# ETRX_RECU.net
KiCad netlist of a schematic drawn in Altium Designer
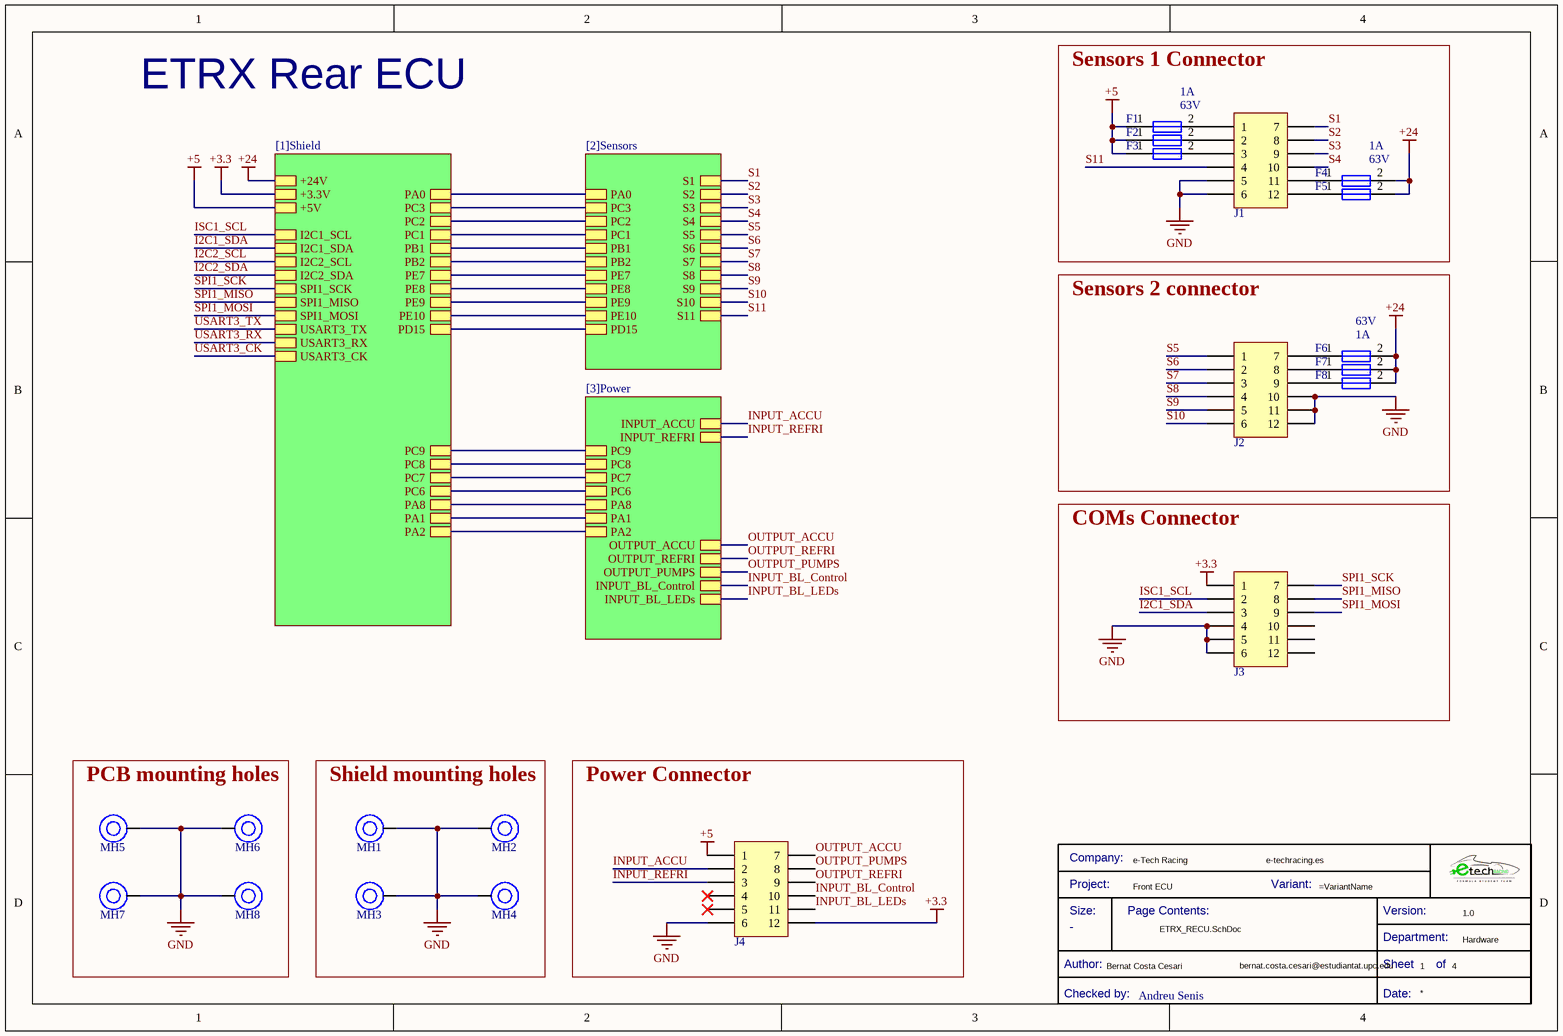
[diagram p0: ETRX_RECU.SchDoc]

(export (version "E")
  (design (tool "Eeschema 10.0.6"))
  (components
    (comp (ref "F1")
      (value "0437001.WRA")
      (footprint "Fuse_1206")
      (description "Fuse Chip Fast Acting 1A 63V SMD Solder Pad 1206 Ceramic T/R Automotive")
      (fields
        (field (name "MANUFACTURER") "Littelfuse")
        (field (name "CURRENT RATING") "1A")
        (field (name "VOLTAGE RATING (DC)") "63V")
        (field (name ".CREATOR") "DO")
      )
      (libsource (lib "Filter components") (part "Fuse_1A_63V_1206"))
    )
    (comp (ref "F2")
      (value "0437001.WRA")
      (footprint "Fuse_1206")
      (description "Fuse Chip Fast Acting 1A 63V SMD Solder Pad 1206 Ceramic T/R Automotive")
      (fields (field (name "MANUFACTURER") "Littelfuse") (field (name ".CREATOR") "DO"))
      (libsource (lib "Filter components") (part "Fuse_1A_63V_1206"))
    )
    (comp (ref "F3")
      (value "0437001.WRA")
      (footprint "Fuse_1206")
      (description "Fuse Chip Fast Acting 1A 63V SMD Solder Pad 1206 Ceramic T/R Automotive")
      (fields (field (name "MANUFACTURER") "Littelfuse") (field (name ".CREATOR") "DO"))
      (libsource (lib "Filter components") (part "Fuse_1A_63V_1206"))
    )
    (comp (ref "F4")
      (value "0437001.WRA")
      (footprint "Fuse_1206")
      (description "Fuse Chip Fast Acting 1A 63V SMD Solder Pad 1206 Ceramic T/R Automotive")
      (fields
        (field (name "MANUFACTURER") "Littelfuse")
        (field (name "CURRENT RATING") "1A")
        (field (name "VOLTAGE RATING (DC)") "63V")
        (field (name ".CREATOR") "DO")
      )
      (libsource (lib "Filter components") (part "Fuse_1A_63V_1206"))
    )
    (comp (ref "F5")
      (value "0437001.WRA")
      (footprint "Fuse_1206")
      (description "Fuse Chip Fast Acting 1A 63V SMD Solder Pad 1206 Ceramic T/R Automotive")
      (fields (field (name "MANUFACTURER") "Littelfuse") (field (name ".CREATOR") "DO"))
      (libsource (lib "Filter components") (part "Fuse_1A_63V_1206"))
    )
    (comp (ref "F6")
      (value "0437001.WRA")
      (footprint "Fuse_1206")
      (description "Fuse Chip Fast Acting 1A 63V SMD Solder Pad 1206 Ceramic T/R Automotive")
      (fields
        (field (name "MANUFACTURER") "Littelfuse")
        (field (name "CURRENT RATING") "1A")
        (field (name "VOLTAGE RATING (DC)") "63V")
        (field (name ".CREATOR") "DO")
      )
      (libsource (lib "Filter components") (part "Fuse_1A_63V_1206"))
    )
    (comp (ref "F7")
      (value "0437001.WRA")
      (footprint "Fuse_1206")
      (description "Fuse Chip Fast Acting 1A 63V SMD Solder Pad 1206 Ceramic T/R Automotive")
      (fields (field (name "MANUFACTURER") "Littelfuse") (field (name ".CREATOR") "DO"))
      (libsource (lib "Filter components") (part "Fuse_1A_63V_1206"))
    )
    (comp (ref "F8")
      (value "0437001.WRA")
      (footprint "Fuse_1206")
      (description "Fuse Chip Fast Acting 1A 63V SMD Solder Pad 1206 Ceramic T/R Automotive")
      (fields (field (name "MANUFACTURER") "Littelfuse") (field (name ".CREATOR") "DO"))
      (libsource (lib "Filter components") (part "Fuse_1A_63V_1206"))
    )
    (comp (ref "J1")
      (value "1053101112")
      (footprint "J_NanoFit_2x6_V")
      (libsource (lib "Electromechanical") (part "J_NanoFit_2x6_V"))
    )
    (comp (ref "J2")
      (value "1053101112")
      (footprint "J_NanoFit_2x6_V")
      (libsource (lib "Electromechanical") (part "J_NanoFit_2x6_V"))
    )
    (comp (ref "J3")
      (value "1053101112")
      (footprint "J_NanoFit_2x6_V")
      (libsource (lib "Electromechanical") (part "J_NanoFit_2x6_V"))
    )
    (comp (ref "J4")
      (value "1053101112")
      (footprint "J_NanoFit_2x6_V")
      (libsource (lib "Electromechanical") (part "J_NanoFit_2x6_V"))
    )
    (comp (ref "MH1")
      (value "Mounting_Hole_M3")
      (footprint "Mounting_Hole_M3")
      (libsource (lib "Electromechanical") (part "Mounting_Hole_M3"))
    )
    (comp (ref "MH2")
      (value "Mounting_Hole_M3")
      (footprint "Mounting_Hole_M3")
      (libsource (lib "Electromechanical") (part "Mounting_Hole_M3"))
    )
    (comp (ref "MH3")
      (value "Mounting_Hole_M3")
      (footprint "Mounting_Hole_M3")
      (libsource (lib "Electromechanical") (part "Mounting_Hole_M3"))
    )
    (comp (ref "MH4")
      (value "Mounting_Hole_M3")
      (footprint "Mounting_Hole_M3")
      (libsource (lib "Electromechanical") (part "Mounting_Hole_M3"))
    )
    (comp (ref "MH5")
      (value "Mounting_Hole_M4")
      (footprint "Mounting_Hole_M4")
      (libsource (lib "Electromechanical") (part "Mounting_Hole_M4"))
    )
    (comp (ref "MH6")
      (value "Mounting_Hole_M4")
      (footprint "Mounting_Hole_M4")
      (libsource (lib "Electromechanical") (part "Mounting_Hole_M4"))
    )
    (comp (ref "MH7")
      (value "Mounting_Hole_M4")
      (footprint "Mounting_Hole_M4")
      (libsource (lib "Electromechanical") (part "Mounting_Hole_M4"))
    )
    (comp (ref "MH8")
      (value "Mounting_Hole_M4")
      (footprint "Mounting_Hole_M4")
      (libsource (lib "Electromechanical") (part "Mounting_Hole_M4"))
    )
  )
  (nets
    (net (code "1") (name "+3.3") (class "Default")
      (node (ref "J3") (pin "1") (pinfunction "1_1") (pintype "passive"))
      (node (ref "J4") (pin "12") (pinfunction "12_12") (pintype "passive"))
    )
    (net (code "2") (name "+5") (class "Default")
      (node (ref "F1") (pin "1") (pinfunction "1_1") (pintype "passive"))
      (node (ref "F2") (pin "1") (pinfunction "1_1") (pintype "passive"))
      (node (ref "F3") (pin "1") (pinfunction "1_1") (pintype "passive"))
      (node (ref "J4") (pin "1") (pinfunction "1_1") (pintype "passive"))
    )
    (net (code "3") (name "+24") (class "Default")
      (node (ref "F4") (pin "2") (pinfunction "2_2") (pintype "passive"))
      (node (ref "F5") (pin "2") (pinfunction "2_2") (pintype "passive"))
      (node (ref "F6") (pin "2") (pinfunction "2_2") (pintype "passive"))
      (node (ref "F7") (pin "2") (pinfunction "2_2") (pintype "passive"))
      (node (ref "F8") (pin "2") (pinfunction "2_2") (pintype "passive"))
    )
    (net (code "4") (name "/I2C1_SDA") (class "Default")
      (node (ref "J3") (pin "3") (pinfunction "3_3") (pintype "passive"))
    )
    (net (code "7") (name "/INPUT_ACCU") (class "Default")
      (node (ref "J4") (pin "2") (pinfunction "2_2") (pintype "passive"))
    )
    (net (code "8") (name "/INPUT_BL_Control") (class "Default")
      (node (ref "J4") (pin "10") (pinfunction "10_10") (pintype "passive"))
    )
    (net (code "9") (name "/INPUT_BL_LEDs") (class "Default")
      (node (ref "J4") (pin "11") (pinfunction "11_11") (pintype "passive"))
    )
    (net (code "10") (name "/INPUT_REFRI") (class "Default")
      (node (ref "J4") (pin "3") (pinfunction "3_3") (pintype "passive"))
    )
    (net (code "11") (name "/ISC1_SCL") (class "Default")
      (node (ref "J3") (pin "2") (pinfunction "2_2") (pintype "passive"))
    )
    (net (code "12") (name "/OUTPUT_ACCU") (class "Default")
      (node (ref "J4") (pin "7") (pinfunction "7_7") (pintype "passive"))
    )
    (net (code "13") (name "/OUTPUT_PUMPS") (class "Default")
      (node (ref "J4") (pin "8") (pinfunction "8_8") (pintype "passive"))
    )
    (net (code "14") (name "/OUTPUT_REFRI") (class "Default")
      (node (ref "J4") (pin "9") (pinfunction "9_9") (pintype "passive"))
    )
    (net (code "33") (name "/S1") (class "Default")
      (node (ref "J1") (pin "7") (pinfunction "7_7") (pintype "passive"))
    )
    (net (code "34") (name "/S2") (class "Default")
      (node (ref "J1") (pin "8") (pinfunction "8_8") (pintype "passive"))
    )
    (net (code "35") (name "/S3") (class "Default")
      (node (ref "J1") (pin "9") (pinfunction "9_9") (pintype "passive"))
    )
    (net (code "36") (name "/S4") (class "Default")
      (node (ref "J1") (pin "10") (pinfunction "10_10") (pintype "passive"))
    )
    (net (code "37") (name "/S5") (class "Default")
      (node (ref "J2") (pin "1") (pinfunction "1_1") (pintype "passive"))
    )
    (net (code "38") (name "/S6") (class "Default")
      (node (ref "J2") (pin "2") (pinfunction "2_2") (pintype "passive"))
    )
    (net (code "39") (name "/S7") (class "Default")
      (node (ref "J2") (pin "3") (pinfunction "3_3") (pintype "passive"))
    )
    (net (code "40") (name "/S8") (class "Default")
      (node (ref "J2") (pin "4") (pinfunction "4_4") (pintype "passive"))
    )
    (net (code "41") (name "/S9") (class "Default")
      (node (ref "J2") (pin "5") (pinfunction "5_5") (pintype "passive"))
    )
    (net (code "42") (name "/S10") (class "Default")
      (node (ref "J2") (pin "6") (pinfunction "6_6") (pintype "passive"))
    )
    (net (code "43") (name "/S11") (class "Default")
      (node (ref "J1") (pin "4") (pinfunction "4_4") (pintype "passive"))
    )
    (net (code "44") (name "/SPI1_MISO") (class "Default")
      (node (ref "J3") (pin "8") (pinfunction "8_8") (pintype "passive"))
    )
    (net (code "45") (name "/SPI1_MOSI") (class "Default")
      (node (ref "J3") (pin "9") (pinfunction "9_9") (pintype "passive"))
    )
    (net (code "46") (name "/SPI1_SCK") (class "Default")
      (node (ref "J3") (pin "7") (pinfunction "7_7") (pintype "passive"))
    )
    (net (code "50") (name "GND") (class "Default")
      (node (ref "J1") (pin "5") (pinfunction "5_5") (pintype "passive"))
      (node (ref "J1") (pin "6") (pinfunction "6_6") (pintype "passive"))
      (node (ref "J2") (pin "10") (pinfunction "10_10") (pintype "passive"))
      (node (ref "J2") (pin "11") (pinfunction "11_11") (pintype "passive"))
      (node (ref "J2") (pin "12") (pinfunction "12_12") (pintype "passive"))
      (node (ref "J3") (pin "4") (pinfunction "4_4") (pintype "passive"))
      (node (ref "J3") (pin "5") (pinfunction "5_5") (pintype "passive"))
      (node (ref "J3") (pin "6") (pinfunction "6_6") (pintype "passive"))
      (node (ref "J4") (pin "6") (pinfunction "6_6") (pintype "passive"))
      (node (ref "MH1") (pin "1") (pinfunction "1_1") (pintype "passive"))
      (node (ref "MH2") (pin "1") (pinfunction "1_1") (pintype "passive"))
      (node (ref "MH3") (pin "1") (pinfunction "1_1") (pintype "passive"))
      (node (ref "MH4") (pin "1") (pinfunction "1_1") (pintype "passive"))
      (node (ref "MH5") (pin "1") (pinfunction "1_1") (pintype "passive"))
      (node (ref "MH6") (pin "1") (pinfunction "1_1") (pintype "passive"))
      (node (ref "MH7") (pin "1") (pinfunction "1_1") (pintype "passive"))
      (node (ref "MH8") (pin "1") (pinfunction "1_1") (pintype "passive"))
    )
    (net (code "51") (name "Net-(F1-Pad2)") (class "Default")
      (node (ref "F1") (pin "2") (pinfunction "2_2") (pintype "passive"))
      (node (ref "J1") (pin "1") (pinfunction "1_1") (pintype "passive"))
    )
    (net (code "52") (name "Net-(F2-Pad2)") (class "Default")
      (node (ref "F2") (pin "2") (pinfunction "2_2") (pintype "passive"))
      (node (ref "J1") (pin "2") (pinfunction "2_2") (pintype "passive"))
    )
    (net (code "53") (name "Net-(F3-Pad2)") (class "Default")
      (node (ref "F3") (pin "2") (pinfunction "2_2") (pintype "passive"))
      (node (ref "J1") (pin "3") (pinfunction "3_3") (pintype "passive"))
    )
    (net (code "54") (name "Net-(F4-Pad1)") (class "Default")
      (node (ref "F4") (pin "1") (pinfunction "1_1") (pintype "passive"))
      (node (ref "J1") (pin "11") (pinfunction "11_11") (pintype "passive"))
    )
    (net (code "55") (name "Net-(F5-Pad1)") (class "Default")
      (node (ref "F5") (pin "1") (pinfunction "1_1") (pintype "passive"))
      (node (ref "J1") (pin "12") (pinfunction "12_12") (pintype "passive"))
    )
    (net (code "56") (name "Net-(F6-Pad1)") (class "Default")
      (node (ref "F6") (pin "1") (pinfunction "1_1") (pintype "passive"))
      (node (ref "J2") (pin "7") (pinfunction "7_7") (pintype "passive"))
    )
    (net (code "57") (name "Net-(F7-Pad1)") (class "Default")
      (node (ref "F7") (pin "1") (pinfunction "1_1") (pintype "passive"))
      (node (ref "J2") (pin "8") (pinfunction "8_8") (pintype "passive"))
    )
    (net (code "58") (name "Net-(F8-Pad1)") (class "Default")
      (node (ref "F8") (pin "1") (pinfunction "1_1") (pintype "passive"))
      (node (ref "J2") (pin "9") (pinfunction "9_9") (pintype "passive"))
    )
    (net (code "59") (name "unconnected-(J3-Pad10)") (class "Default")
      (node (ref "J3") (pin "10") (pinfunction "10_10") (pintype "passive"))
    )
    (net (code "60") (name "unconnected-(J3-Pad11)") (class "Default")
      (node (ref "J3") (pin "11") (pinfunction "11_11") (pintype "passive"))
    )
    (net (code "61") (name "unconnected-(J3-Pad12)") (class "Default")
      (node (ref "J3") (pin "12") (pinfunction "12_12") (pintype "passive"))
    )
    (net (code "62") (name "unconnected-(J4-Pad4)") (class "Default")
      (node (ref "J4") (pin "4") (pinfunction "4_4") (pintype "passive+no_connect"))
    )
    (net (code "63") (name "unconnected-(J4-Pad5)") (class "Default")
      (node (ref "J4") (pin "5") (pinfunction "5_5") (pintype "passive+no_connect"))
    )
  )
)
